# current_unit.net
KiCad netlist of a schematic drawn in Altium Designer
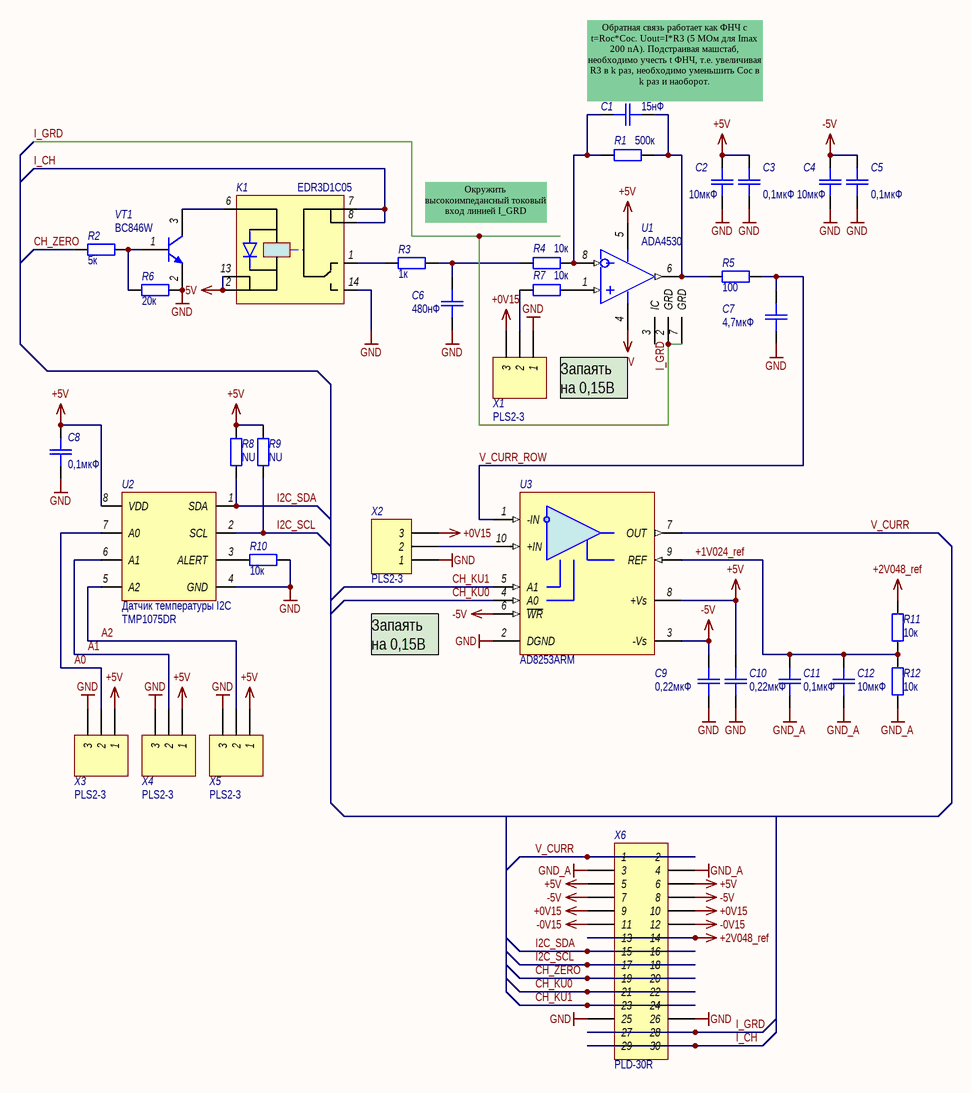
[diagram p0: current_unit.SchDoc]

(export (version "E")
  (design (tool "Eeschema 10.0.6"))
  (components
    (comp (ref "C1")
      (value "15нФ")
      (footprint "CR-0805")
      (description "Конденсатор для поверхностного монтажа")
      (libsource (lib "my_passive") (part "C_smd"))
    )
    (comp (ref "C2")
      (value "10мкФ")
      (footprint "CR-0805")
      (description "Конденсатор для поверхностного монтажа")
      (libsource (lib "my_passive") (part "C_smd"))
    )
    (comp (ref "C3")
      (value "0,1мкФ")
      (footprint "CR-0805")
      (description "Конденсатор для поверхностного монтажа")
      (libsource (lib "my_passive") (part "C_smd"))
    )
    (comp (ref "C4")
      (value "10мкФ")
      (footprint "CR-0805")
      (description "Конденсатор для поверхностного монтажа")
      (libsource (lib "my_passive") (part "C_smd"))
    )
    (comp (ref "C5")
      (value "0,1мкФ")
      (footprint "CR-0805")
      (description "Конденсатор для поверхностного монтажа")
      (libsource (lib "my_passive") (part "C_smd"))
    )
    (comp (ref "C6")
      (value "480нФ")
      (footprint "CR-0805")
      (description "Конденсатор для поверхностного монтажа")
      (libsource (lib "my_passive") (part "C_smd"))
    )
    (comp (ref "C7")
      (value "4,7мкФ")
      (footprint "CR-0805")
      (description "Конденсатор для поверхностного монтажа")
      (libsource (lib "my_passive") (part "C_smd"))
    )
    (comp (ref "C8")
      (value "0,1мкФ")
      (footprint "CR-0805")
      (description "Конденсатор для поверхностного монтажа")
      (libsource (lib "my_passive") (part "C_smd"))
    )
    (comp (ref "C9")
      (value "0,22мкФ")
      (footprint "CR-0805")
      (description "Конденсатор для поверхностного монтажа")
      (libsource (lib "my_passive") (part "C_smd"))
    )
    (comp (ref "C10")
      (value "0,22мкФ")
      (footprint "CR-0805")
      (description "Конденсатор для поверхностного монтажа")
      (libsource (lib "my_passive") (part "C_smd"))
    )
    (comp (ref "C11")
      (value "0,1мкФ")
      (footprint "CR-0805")
      (description "Конденсатор для поверхностного монтажа")
      (libsource (lib "my_passive") (part "C_smd"))
    )
    (comp (ref "C12")
      (value "10мкФ")
      (footprint "CR-0805")
      (description "Конденсатор для поверхностного монтажа")
      (libsource (lib "my_passive") (part "C_smd"))
    )
    (comp (ref "K1")
      (value "EDR3D1C05")
      (footprint "SOP-14")
      (description "Reed Relay")
      (libsource (lib "my_commutator") (part "EDR3D1C05"))
    )
    (comp (ref "R1")
      (value "500к")
      (footprint "CR-0805")
      (description "Резистор для поверхностного монтажа")
      (libsource (lib "my_passive") (part "R_smd"))
    )
    (comp (ref "R2")
      (value "5к")
      (footprint "CR-0805")
      (description "Резистор для поверхностного монтажа")
      (libsource (lib "my_passive") (part "R_smd"))
    )
    (comp (ref "R3")
      (value "1к")
      (footprint "CR-0805")
      (description "Резистор для поверхностного монтажа")
      (libsource (lib "my_passive") (part "R_smd"))
    )
    (comp (ref "R4")
      (value "10к")
      (footprint "CR-0805")
      (description "Резистор для поверхностного монтажа")
      (libsource (lib "my_passive") (part "R_smd"))
    )
    (comp (ref "R5")
      (value "100")
      (footprint "CR-0805")
      (description "Резистор для поверхностного монтажа")
      (libsource (lib "my_passive") (part "R_smd"))
    )
    (comp (ref "R6")
      (value "20к")
      (footprint "CR-0805")
      (description "Резистор для поверхностного монтажа")
      (libsource (lib "my_passive") (part "R_smd"))
    )
    (comp (ref "R7")
      (value "10к")
      (footprint "CR-0805")
      (description "Резистор для поверхностного монтажа")
      (libsource (lib "my_passive") (part "R_smd"))
    )
    (comp (ref "R8")
      (value "NU")
      (footprint "CR-0805")
      (description "Резистор для поверхностного монтажа")
      (libsource (lib "") (part "R_smd_1"))
    )
    (comp (ref "R9")
      (value "NU")
      (footprint "CR-0805")
      (description "Резистор для поверхностного монтажа")
      (libsource (lib "") (part "R_smd_1"))
    )
    (comp (ref "R10")
      (value "10к")
      (footprint "CR-0805")
      (description "Резистор для поверхностного монтажа")
      (libsource (lib "") (part "R_smd_2"))
    )
    (comp (ref "R11")
      (value "10к")
      (footprint "CR-0805")
      (description "Резистор для поверхностного монтажа")
      (libsource (lib "") (part "R_smd_1"))
    )
    (comp (ref "R12")
      (value "10к")
      (footprint "CR-0805")
      (description "Резистор для поверхностного монтажа")
      (libsource (lib "") (part "R_smd_3"))
    )
    (comp (ref "U1")
      (value "ADA4530-1")
      (footprint "SOIC-8")
      (description "Ultra-Low Bias Current Difet OpAmp")
      (fields (field (name "НАИМЕНОВАНИЕ") "ADA4530"))
      (libsource (lib "my_op_amplifier") (part "ADA4530"))
    )
    (comp (ref "U2")
      (value "TMP1075")
      (footprint "SOIC-8")
      (description "TMP1075 Temperature Sensor With I2C and SMBus Interface")
      (fields (field (name "НАЗНАЧЕНИЕ") "Датчик температуры I2C") (field (name "НАИМЕНОВАНИЕ") "TMP1075DR"))
      (libsource (lib "my_sensor") (part "TMP1075"))
    )
    (comp (ref "U3")
      (value "AD8253ARM")
      (footprint "MSOP-10")
      (description "10 MHz, 20 V/мs, G = 1, 10, 100, 1000 iCMOS Programmable Gain Instrumentation Amplifier")
      (fields (field (name "НАИМЕНОВАНИЕ") "AD8253ARM"))
      (libsource (lib "my_op_amplifier") (part "AD8253"))
    )
    (comp (ref "VT1")
      (value "BC846BWT1")
      (footprint "SOT-23")
      (description "General Purpose Transistor, NPN Silicon, 3-Pin SC70, Tape and Reel")
      (fields (field (name "MANUFACTURER") "On Semiconductor") (field (name "НАИМЕНОВАНИЕ") "BC846W"))
      (libsource (lib "my_semicond") (part "BC846BWT1"))
    )
    (comp (ref "X1")
      (value "MHDR1X3")
      (footprint "SJMP-3")
      (description "Header, 3-Pin")
      (fields (field (name "НАИМЕНОВАНИЕ") "PLS2-3") (field (name "PUBLISHER") "Altium Limited"))
      (libsource (lib "my_connector") (part "MHDR1X3"))
    )
    (comp (ref "X2")
      (value "MHDR1X3")
      (footprint "SJMP-3")
      (description "Header, 3-Pin")
      (fields (field (name "НАИМЕНОВАНИЕ") "PLS2-3") (field (name "PUBLISHER") "Altium Limited"))
      (libsource (lib "") (part "MHDR1X3_1"))
    )
    (comp (ref "X3")
      (value "MHDR1X3")
      (footprint "SJMP-3")
      (description "Header, 3-Pin")
      (fields (field (name "НАИМЕНОВАНИЕ") "PLS2-3") (field (name "PUBLISHER") "Altium Limited"))
      (libsource (lib "my_connector") (part "MHDR1X3"))
    )
    (comp (ref "X4")
      (value "MHDR1X3")
      (footprint "SJMP-3")
      (description "Header, 3-Pin")
      (fields (field (name "НАИМЕНОВАНИЕ") "PLS2-3") (field (name "PUBLISHER") "Altium Limited"))
      (libsource (lib "my_connector") (part "MHDR1X3"))
    )
    (comp (ref "X5")
      (value "MHDR1X3")
      (footprint "SJMP-3")
      (description "Header, 3-Pin")
      (fields (field (name "НАИМЕНОВАНИЕ") "PLS2-3") (field (name "PUBLISHER") "Altium Limited"))
      (libsource (lib "my_connector") (part "MHDR1X3"))
    )
    (comp (ref "X6")
      (value "HDR2X15")
      (footprint "HDR2X15")
      (description "Header, 15-Pin, Dual row")
      (fields (field (name "НАИМЕНОВАНИЕ") "PLD-30R") (field (name "PUBLISHER") "Altium Limited"))
      (libsource (lib "my_connector") (part "HDR2X15"))
    )
  )
  (nets
    (net (code "1") (name "+0V15") (class "Default")
      (node (ref "X1") (pin "3") (pinfunction "3_3") (pintype "passive"))
      (node (ref "X2") (pin "3") (pinfunction "3_3") (pintype "passive"))
      (node (ref "X6") (pin "10") (pinfunction "10_10") (pintype "passive"))
      (node (ref "X6") (pin "9") (pinfunction "9_9") (pintype "passive"))
    )
    (net (code "2") (name "+2V048_ref") (class "Default")
      (node (ref "R11") (pin "1") (pinfunction "1_1") (pintype "passive"))
      (node (ref "X6") (pin "13") (pinfunction "13_13") (pintype "passive"))
      (node (ref "X6") (pin "14") (pinfunction "14_14") (pintype "passive"))
    )
    (net (code "3") (name "+5V") (class "Default")
      (node (ref "C10") (pin "2") (pinfunction "2_2") (pintype "passive"))
      (node (ref "C2") (pin "2") (pinfunction "2_2") (pintype "passive"))
      (node (ref "C3") (pin "2") (pinfunction "2_2") (pintype "passive"))
      (node (ref "C8") (pin "2") (pinfunction "2_2") (pintype "passive"))
      (node (ref "K1") (pin "13") (pintype "passive"))
      (node (ref "K1") (pin "2") (pintype "passive"))
      (node (ref "R8") (pin "1") (pinfunction "1_1") (pintype "passive"))
      (node (ref "R9") (pin "1") (pinfunction "1_1") (pintype "passive"))
      (node (ref "U1") (pin "5") (pinfunction "V+_5") (pintype "power_in"))
      (node (ref "U2") (pin "8") (pinfunction "VDD_8") (pintype "passive"))
      (node (ref "U3") (pin "8") (pinfunction "+Vs_8") (pintype "power_in"))
      (node (ref "X3") (pin "1") (pinfunction "1_1") (pintype "passive"))
      (node (ref "X4") (pin "1") (pinfunction "1_1") (pintype "passive"))
      (node (ref "X5") (pin "1") (pinfunction "1_1") (pintype "passive"))
      (node (ref "X6") (pin "5") (pinfunction "5_5") (pintype "passive"))
      (node (ref "X6") (pin "6") (pinfunction "6_6") (pintype "passive"))
    )
    (net (code "4") (name "-0V15") (class "Default")
      (node (ref "X6") (pin "11") (pinfunction "11_11") (pintype "passive"))
      (node (ref "X6") (pin "12") (pinfunction "12_12") (pintype "passive"))
    )
    (net (code "5") (name "-5V") (class "Default")
      (node (ref "C4") (pin "2") (pinfunction "2_2") (pintype "passive"))
      (node (ref "C5") (pin "2") (pinfunction "2_2") (pintype "passive"))
      (node (ref "C9") (pin "2") (pinfunction "2_2") (pintype "passive"))
      (node (ref "U1") (pin "4") (pinfunction "V-_4") (pintype "power_in"))
      (node (ref "U3") (pin "3") (pinfunction "-Vs_3") (pintype "power_in"))
      (node (ref "U3") (pin "6") (pinfunction "~{WR}_6") (pintype "input"))
      (node (ref "X6") (pin "7") (pinfunction "7_7") (pintype "passive"))
      (node (ref "X6") (pin "8") (pinfunction "8_8") (pintype "passive"))
    )
    (net (code "6") (name "/+1V024_ref") (class "Default")
      (node (ref "C11") (pin "2") (pinfunction "2_2") (pintype "passive"))
      (node (ref "C12") (pin "2") (pinfunction "2_2") (pintype "passive"))
      (node (ref "R11") (pin "2") (pinfunction "2_2") (pintype "passive"))
      (node (ref "R12") (pin "2") (pinfunction "2_2") (pintype "passive"))
      (node (ref "U3") (pin "9") (pinfunction "REF_9") (pintype "input"))
    )
    (net (code "7") (name "/A0") (class "Default")
      (node (ref "U2") (pin "7") (pinfunction "A0_7") (pintype "passive"))
      (node (ref "X3") (pin "2") (pinfunction "2_2") (pintype "passive"))
    )
    (net (code "8") (name "/A1") (class "Default")
      (node (ref "U2") (pin "6") (pinfunction "A1_6") (pintype "passive"))
      (node (ref "X4") (pin "2") (pinfunction "2_2") (pintype "passive"))
    )
    (net (code "9") (name "/A2") (class "Default")
      (node (ref "U2") (pin "5") (pinfunction "A2_5") (pintype "passive"))
      (node (ref "X5") (pin "2") (pinfunction "2_2") (pintype "passive"))
    )
    (net (code "10") (name "/CH_KU0") (class "Default")
      (node (ref "U3") (pin "4") (pinfunction "A0_4") (pintype "input"))
      (node (ref "X6") (pin "21") (pinfunction "21_21") (pintype "passive"))
      (node (ref "X6") (pin "22") (pinfunction "22_22") (pintype "passive"))
    )
    (net (code "11") (name "/CH_KU1") (class "Default")
      (node (ref "U3") (pin "5") (pinfunction "A1_5") (pintype "input"))
      (node (ref "X6") (pin "23") (pinfunction "23_23") (pintype "passive"))
      (node (ref "X6") (pin "24") (pinfunction "24_24") (pintype "passive"))
    )
    (net (code "12") (name "/CH_ZERO") (class "Default")
      (node (ref "R2") (pin "2") (pinfunction "2_2") (pintype "passive"))
      (node (ref "X6") (pin "19") (pinfunction "19_19") (pintype "passive"))
      (node (ref "X6") (pin "20") (pinfunction "20_20") (pintype "passive"))
    )
    (net (code "13") (name "/I2C_SCL") (class "Default")
      (node (ref "R9") (pin "2") (pinfunction "2_2") (pintype "passive"))
      (node (ref "U2") (pin "2") (pinfunction "SCL_2") (pintype "passive"))
      (node (ref "X6") (pin "17") (pinfunction "17_17") (pintype "passive"))
      (node (ref "X6") (pin "18") (pinfunction "18_18") (pintype "passive"))
    )
    (net (code "14") (name "/I2C_SDA") (class "Default")
      (node (ref "R8") (pin "2") (pinfunction "2_2") (pintype "passive"))
      (node (ref "U2") (pin "1") (pinfunction "SDA_1") (pintype "passive"))
      (node (ref "X6") (pin "15") (pinfunction "15_15") (pintype "passive"))
      (node (ref "X6") (pin "16") (pinfunction "16_16") (pintype "passive"))
    )
    (net (code "15") (name "/I_CH") (class "Default")
      (node (ref "K1") (pin "7") (pintype "passive"))
      (node (ref "K1") (pin "8") (pintype "passive"))
      (node (ref "X6") (pin "29") (pinfunction "29_29") (pintype "passive"))
      (node (ref "X6") (pin "30") (pinfunction "30_30") (pintype "passive"))
    )
    (net (code "16") (name "/I_GRD") (class "Default")
      (node (ref "U1") (pin "2") (pinfunction "GRD_2") (pintype "passive"))
      (node (ref "U1") (pin "7") (pinfunction "GRD_7") (pintype "passive"))
      (node (ref "X6") (pin "27") (pinfunction "27_27") (pintype "passive"))
      (node (ref "X6") (pin "28") (pinfunction "28_28") (pintype "passive"))
    )
    (net (code "17") (name "/V_CURR") (class "Default")
      (node (ref "U3") (pin "7") (pinfunction "OUT_7") (pintype "output"))
      (node (ref "X6") (pin "1") (pinfunction "1_1") (pintype "passive"))
      (node (ref "X6") (pin "2") (pinfunction "2_2") (pintype "passive"))
    )
    (net (code "18") (name "/V_CURR_ROW") (class "Default")
      (node (ref "C7") (pin "1") (pinfunction "1_1") (pintype "passive"))
      (node (ref "R5") (pin "1") (pinfunction "1_1") (pintype "passive"))
      (node (ref "U3") (pin "1") (pinfunction "-IN_1") (pintype "input"))
    )
    (net (code "19") (name "GND") (class "Default")
      (node (ref "C10") (pin "1") (pinfunction "1_1") (pintype "passive"))
      (node (ref "C2") (pin "1") (pinfunction "1_1") (pintype "passive"))
      (node (ref "C3") (pin "1") (pinfunction "1_1") (pintype "passive"))
      (node (ref "C4") (pin "1") (pinfunction "1_1") (pintype "passive"))
      (node (ref "C5") (pin "1") (pinfunction "1_1") (pintype "passive"))
      (node (ref "C6") (pin "1") (pinfunction "1_1") (pintype "passive"))
      (node (ref "C7") (pin "2") (pinfunction "2_2") (pintype "passive"))
      (node (ref "C8") (pin "1") (pinfunction "1_1") (pintype "passive"))
      (node (ref "C9") (pin "1") (pinfunction "1_1") (pintype "passive"))
      (node (ref "K1") (pin "14") (pintype "passive"))
      (node (ref "R10") (pin "2") (pinfunction "2_2") (pintype "passive"))
      (node (ref "R6") (pin "1") (pinfunction "1_1") (pintype "passive"))
      (node (ref "U2") (pin "4") (pinfunction "GND_4") (pintype "passive"))
      (node (ref "U3") (pin "2") (pinfunction "DGND_2") (pintype "power_in"))
      (node (ref "VT1") (pin "2") (pinfunction "E_2") (pintype "passive"))
      (node (ref "X1") (pin "1") (pinfunction "1_1") (pintype "passive"))
      (node (ref "X2") (pin "1") (pinfunction "1_1") (pintype "passive"))
      (node (ref "X3") (pin "3") (pinfunction "3_3") (pintype "passive"))
      (node (ref "X4") (pin "3") (pinfunction "3_3") (pintype "passive"))
      (node (ref "X5") (pin "3") (pinfunction "3_3") (pintype "passive"))
      (node (ref "X6") (pin "25") (pinfunction "25_25") (pintype "passive"))
      (node (ref "X6") (pin "26") (pinfunction "26_26") (pintype "passive"))
    )
    (net (code "20") (name "GND_A") (class "Default")
      (node (ref "C11") (pin "1") (pinfunction "1_1") (pintype "passive"))
      (node (ref "C12") (pin "1") (pinfunction "1_1") (pintype "passive"))
      (node (ref "R12") (pin "1") (pinfunction "1_1") (pintype "passive"))
      (node (ref "X6") (pin "3") (pinfunction "3_3") (pintype "passive"))
      (node (ref "X6") (pin "4") (pinfunction "4_4") (pintype "passive"))
    )
    (net (code "21") (name "Net-(C6-Pad2)") (class "Default")
      (node (ref "C6") (pin "2") (pinfunction "2_2") (pintype "passive"))
      (node (ref "R3") (pin "1") (pinfunction "1_1") (pintype "passive"))
      (node (ref "R4") (pin "2") (pinfunction "2_2") (pintype "passive"))
    )
    (net (code "22") (name "Net-(K1-Pad1)") (class "Default")
      (node (ref "K1") (pin "1") (pintype "passive"))
      (node (ref "R3") (pin "2") (pinfunction "2_2") (pintype "passive"))
    )
    (net (code "23") (name "Net-(R7-Pad2)") (class "Default")
      (node (ref "R7") (pin "2") (pinfunction "2_2") (pintype "passive"))
      (node (ref "X1") (pin "2") (pinfunction "2_2") (pintype "passive"))
    )
    (net (code "24") (name "Net-(U1-IN+)") (class "Default")
      (node (ref "R7") (pin "1") (pinfunction "1_1") (pintype "passive"))
      (node (ref "U1") (pin "1") (pinfunction "IN+_1") (pintype "input"))
    )
    (net (code "25") (name "Net-(U1-IN-)") (class "Default")
      (node (ref "C1") (pin "2") (pinfunction "2_2") (pintype "passive"))
      (node (ref "R1") (pin "2") (pinfunction "2_2") (pintype "passive"))
      (node (ref "R4") (pin "1") (pinfunction "1_1") (pintype "passive"))
      (node (ref "U1") (pin "8") (pinfunction "IN-_8") (pintype "input"))
    )
    (net (code "26") (name "Net-(U1-OUT)") (class "Default")
      (node (ref "C1") (pin "1") (pinfunction "1_1") (pintype "passive"))
      (node (ref "R1") (pin "1") (pinfunction "1_1") (pintype "passive"))
      (node (ref "R5") (pin "2") (pinfunction "2_2") (pintype "passive"))
      (node (ref "U1") (pin "6") (pinfunction "OUT_6") (pintype "output"))
    )
    (net (code "27") (name "Net-(U2-ALERT)") (class "Default")
      (node (ref "R10") (pin "1") (pinfunction "1_1") (pintype "passive"))
      (node (ref "U2") (pin "3") (pinfunction "ALERT_3") (pintype "passive"))
    )
    (net (code "28") (name "Net-(U3-+IN)") (class "Default")
      (node (ref "U3") (pin "10") (pinfunction "+IN_10") (pintype "input"))
      (node (ref "X2") (pin "2") (pinfunction "2_2") (pintype "passive"))
    )
    (net (code "29") (name "Net-(VT1-B)") (class "Default")
      (node (ref "R2") (pin "1") (pinfunction "1_1") (pintype "passive"))
      (node (ref "R6") (pin "2") (pinfunction "2_2") (pintype "passive"))
      (node (ref "VT1") (pin "1") (pinfunction "B_1") (pintype "passive"))
    )
    (net (code "30") (name "Net-(VT1-C)") (class "Default")
      (node (ref "K1") (pin "6") (pintype "passive"))
      (node (ref "VT1") (pin "3") (pinfunction "C_3") (pintype "passive"))
    )
    (net (code "31") (name "unconnected-(U1-IC-Pad3)") (class "Default")
      (node (ref "U1") (pin "3") (pinfunction "IC_3") (pintype "passive"))
    )
  )
)
